# Power_Supply.net
KiCad netlist of a schematic drawn in Altium Designer
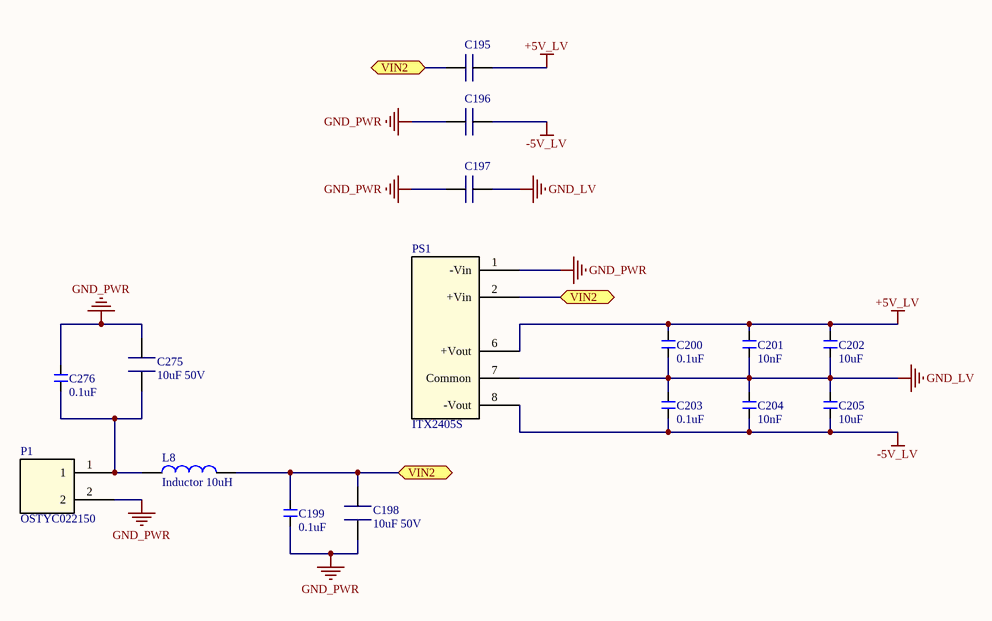
[diagram p0: Power Supply.SchDoc]

(export (version "E")
  (design (tool "Eeschema 10.0.6"))
  (components
    (comp (ref "C195")
      (value "Cap 1812")
      (footprint "1812 (4532 Metric)")
      (description "CAP CER 220PF 3KV C0G 1812")
      (fields (field (name "PART") "445-2380-1-ND"))
      (libsource (lib "Library_Microgrid") (part "Cap 3kV 220pF"))
    )
    (comp (ref "C196")
      (value "Cap 1812")
      (footprint "1812 (4532 Metric)")
      (description "CAP CER 220PF 3KV C0G 1812")
      (fields (field (name "PART") "445-2380-1-ND"))
      (libsource (lib "Library_Microgrid") (part "Cap 3kV 220pF"))
    )
    (comp (ref "C197")
      (value "Cap 1812")
      (footprint "1812 (4532 Metric)")
      (description "CAP CER 220PF 3KV C0G 1812")
      (fields (field (name "PART") "445-2380-1-ND"))
      (libsource (lib "Library_Microgrid") (part "Cap 3kV 220pF"))
    )
    (comp (ref "C198")
      (value "10uF 50V")
      (footprint "1206")
      (description "CAP CER 10UF 50V X5R 1206")
      (fields (field (name "PART") "587-3248-1-ND") (field (name "Comment") "Cap 1206"))
      (libsource (lib "Library_Microgrid") (part "Cap 1206"))
    )
    (comp (ref "C199")
      (value "0.1uF")
      (footprint "0603 (1608 Metric)")
      (description "CAP CER 0.1UF 50V Y5V 0603")
      (fields (field (name "PART") "311-1343-6-ND") (field (name "Comment") "Cap 0603_new"))
      (libsource (lib "Library_Microgrid") (part "Cap 0603_new"))
    )
    (comp (ref "C200")
      (value "0.1uF")
      (footprint "0603 (1608 Metric)")
      (description "CAP CER 0.1UF 50V Y5V 0603")
      (fields (field (name "PART") "311-1343-6-ND") (field (name "Comment") "Cap 0603_new"))
      (libsource (lib "Library_Microgrid") (part "Cap 0603_new"))
    )
    (comp (ref "C201")
      (value "10nF")
      (footprint "0603 (1608 Metric)")
      (description "CAP CER 0603 10NF 50V U2J 5%")
      (fields (field (name "PART") "399-13384-1-ND") (field (name "Comment") "Cap 0603_new"))
      (libsource (lib "Library_Microgrid") (part "Cap 0603_new"))
    )
    (comp (ref "C202")
      (value "10uF")
      (footprint "0603 (1608 Metric)")
      (description "CAP CER 10UF 35V X5R 0805")
      (fields (field (name "PART") "490-10515-1-ND") (field (name "Comment") "Cap 0603_new"))
      (libsource (lib "Library_Microgrid") (part "Cap 0603_new"))
    )
    (comp (ref "C203")
      (value "0.1uF")
      (footprint "0603 (1608 Metric)")
      (description "CAP CER 0.1UF 50V Y5V 0603")
      (fields (field (name "PART") "311-1343-6-ND") (field (name "Comment") "Cap 0603_new"))
      (libsource (lib "Library_Microgrid") (part "Cap 0603_new"))
    )
    (comp (ref "C204")
      (value "10nF")
      (footprint "0603 (1608 Metric)")
      (description "CAP CER 0603 10NF 50V U2J 5%")
      (fields (field (name "PART") "399-13384-1-ND") (field (name "Comment") "Cap 0603_new"))
      (libsource (lib "Library_Microgrid") (part "Cap 0603_new"))
    )
    (comp (ref "C205")
      (value "10uF")
      (footprint "0603 (1608 Metric)")
      (description "CAP CER 10UF 35V X5R 0805")
      (fields (field (name "PART") "490-10515-1-ND") (field (name "Comment") "Cap 0603_new"))
      (libsource (lib "Library_Microgrid") (part "Cap 0603_new"))
    )
    (comp (ref "C275")
      (value "10uF 50V")
      (footprint "1206")
      (description "CAP CER 10UF 50V X5R 1206")
      (fields (field (name "PART") "587-3248-1-ND") (field (name "Comment") "Cap 1206"))
      (libsource (lib "Library_Microgrid") (part "Cap 1206"))
    )
    (comp (ref "C276")
      (value "0.1uF")
      (footprint "0603 (1608 Metric)")
      (description "CAP CER 0.1UF 50V Y5V 0603")
      (fields (field (name "PART") "311-1343-6-ND") (field (name "Comment") "Cap 0603_new"))
      (libsource (lib "Library_Microgrid") (part "Cap 0603_new"))
    )
    (comp (ref "L8")
      (value "Inductor 10uH")
      (footprint "Inductor Surface Mount")
      (description "FIXED IND 10UH 1.19A 110 MOHM")
      (fields (field (name "PART") "732-1103-1-ND"))
      (libsource (lib "Library_Microgrid") (part "Inductor 10uH"))
    )
    (comp (ref "P1")
      (value "OSTYC022150")
      (footprint "2 pin Terminal")
      (description "2 pin Terminal")
      (libsource (lib "Library_Microgrid") (part "2 pin Terminal"))
    )
    (comp (ref "PS1")
      (value "ITX2405S")
      (footprint "8 SIP")
      (description "DC/DC CONVERTER +/-5V 6W")
      (fields (field (name "PART") "1470-2542-5-ND"))
      (libsource (lib "Library_Microgrid") (part "ITX2405S"))
    )
  )
  (nets
    (net (code "1") (name "+5V_LV") (class "Default")
      (node (ref "C195") (pin "2") (pinfunction "OUT_2") (pintype "passive"))
      (node (ref "C200") (pin "2") (pinfunction "OUT_2") (pintype "passive"))
      (node (ref "C201") (pin "2") (pinfunction "OUT_2") (pintype "passive"))
      (node (ref "C202") (pin "2") (pinfunction "OUT_2") (pintype "passive"))
      (node (ref "PS1") (pin "6") (pinfunction "+Vout_6") (pintype "passive"))
    )
    (net (code "2") (name "-5V_LV") (class "Default")
      (node (ref "C196") (pin "2") (pinfunction "OUT_2") (pintype "passive"))
      (node (ref "C203") (pin "1") (pinfunction "OUT_1") (pintype "passive"))
      (node (ref "C204") (pin "1") (pinfunction "OUT_1") (pintype "passive"))
      (node (ref "C205") (pin "1") (pinfunction "OUT_1") (pintype "passive"))
      (node (ref "PS1") (pin "8") (pinfunction "-Vout_8") (pintype "passive"))
    )
    (net (code "3") (name "/VIN2") (class "Default")
      (node (ref "C195") (pin "1") (pinfunction "OUT_1") (pintype "passive"))
      (node (ref "C198") (pin "2") (pinfunction "OUT_2") (pintype "passive"))
      (node (ref "C199") (pin "2") (pinfunction "OUT_2") (pintype "passive"))
      (node (ref "L8") (pin "2") (pinfunction "OUT_2") (pintype "passive"))
      (node (ref "PS1") (pin "2") (pinfunction "+Vin_2") (pintype "passive"))
    )
    (net (code "4") (name "GND_LV") (class "Default")
      (node (ref "C197") (pin "2") (pinfunction "OUT_2") (pintype "passive"))
      (node (ref "C200") (pin "1") (pinfunction "OUT_1") (pintype "passive"))
      (node (ref "C201") (pin "1") (pinfunction "OUT_1") (pintype "passive"))
      (node (ref "C202") (pin "1") (pinfunction "OUT_1") (pintype "passive"))
      (node (ref "C203") (pin "2") (pinfunction "OUT_2") (pintype "passive"))
      (node (ref "C204") (pin "2") (pinfunction "OUT_2") (pintype "passive"))
      (node (ref "C205") (pin "2") (pinfunction "OUT_2") (pintype "passive"))
      (node (ref "PS1") (pin "7") (pinfunction "Common_7") (pintype "passive"))
    )
    (net (code "5") (name "GND_PWR") (class "Default")
      (node (ref "C196") (pin "1") (pinfunction "OUT_1") (pintype "passive"))
      (node (ref "C197") (pin "1") (pinfunction "OUT_1") (pintype "passive"))
      (node (ref "C198") (pin "1") (pinfunction "OUT_1") (pintype "passive"))
      (node (ref "C199") (pin "1") (pinfunction "OUT_1") (pintype "passive"))
      (node (ref "C275") (pin "2") (pinfunction "OUT_2") (pintype "passive"))
      (node (ref "C276") (pin "2") (pinfunction "OUT_2") (pintype "passive"))
      (node (ref "P1") (pin "2") (pinfunction "2_2") (pintype "passive"))
      (node (ref "PS1") (pin "1") (pinfunction "-Vin_1") (pintype "passive"))
    )
    (net (code "6") (name "Net-(C275-OUT-Pad1)") (class "Default")
      (node (ref "C275") (pin "1") (pinfunction "OUT_1") (pintype "passive"))
      (node (ref "C276") (pin "1") (pinfunction "OUT_1") (pintype "passive"))
      (node (ref "L8") (pin "1") (pinfunction "OUT_1") (pintype "passive"))
      (node (ref "P1") (pin "1") (pinfunction "1_1") (pintype "passive"))
    )
  )
)
